# Main.net
KiCad netlist of a schematic drawn in Altium Designer
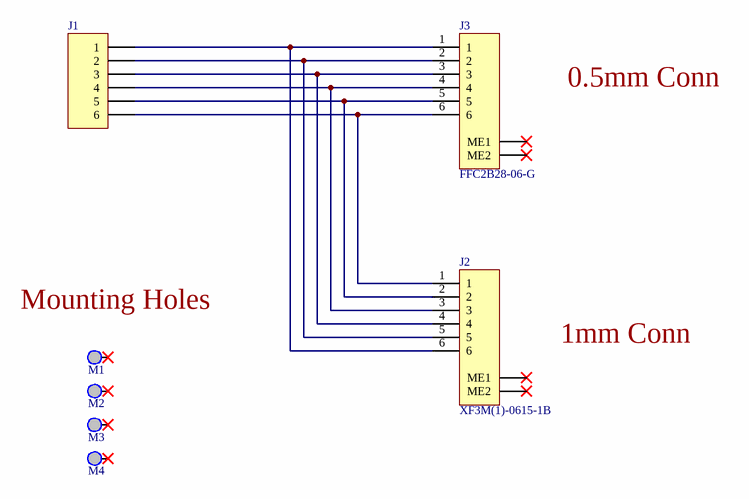
[diagram p0: Main.SchDoc]

(export (version "E")
  (design (tool "Eeschema 10.0.6"))
  (components
    (comp (ref "J1")
      (value "61300611121")
      (footprint "HDR-V-1X6")
      (description "Header, 6-Pin, 0.1\"")
      (libsource (lib "intercreate") (part "HDR-V-1X6-M"))
    )
    (comp (ref "J2")
      (value "XF3M(1)-0615-1B")
      (footprint "CONN-FFC-H-6P-1MM")
      (description "1.0-mm Pitch, Dual Contact ; For FPC/FFC, 6 Contacts, RoHS")
      (libsource (lib "intercreate") (part "CONN-FFC-H-6P-1MM"))
    )
    (comp (ref "J3")
      (value "FFC2B28-06-G")
      (footprint "CONN-FFC-H-6P-0.5MM")
      (description "6 Position FFC, FPC Connector Contacts, Top and Bottom 0.020\" (0.50mm) Surface Mount, Right Angle")
      (libsource (lib "intercreate") (part "CONN-FFC-H-6P-0.5MM"))
    )
    (comp (ref "M1")
      (value "MTG_HOLE")
      (footprint "MH_P_2.5MM")
      (description "MTG HOLE PLATED VARIOUS SIZES")
      (libsource (lib "intercreate") (part "MTG_HOLE"))
    )
    (comp (ref "M2")
      (value "MTG_HOLE")
      (footprint "MH_P_2.5MM")
      (description "MTG HOLE PLATED VARIOUS SIZES")
      (libsource (lib "intercreate") (part "MTG_HOLE"))
    )
    (comp (ref "M3")
      (value "MTG_HOLE")
      (footprint "MH_P_2.5MM")
      (description "MTG HOLE PLATED VARIOUS SIZES")
      (libsource (lib "intercreate") (part "MTG_HOLE"))
    )
    (comp (ref "M4")
      (value "MTG_HOLE")
      (footprint "MH_P_2.5MM")
      (description "MTG HOLE PLATED VARIOUS SIZES")
      (libsource (lib "intercreate") (part "MTG_HOLE"))
    )
  )
  (nets
    (net (code "1") (name "Net-(J1-Pad1)") (class "Default")
      (node (ref "J1") (pin "1") (pinfunction "1_1") (pintype "passive"))
      (node (ref "J2") (pin "6") (pinfunction "6_6") (pintype "passive"))
      (node (ref "J3") (pin "1") (pinfunction "1_1") (pintype "passive"))
    )
    (net (code "2") (name "Net-(J1-Pad2)") (class "Default")
      (node (ref "J1") (pin "2") (pinfunction "2_2") (pintype "passive"))
      (node (ref "J2") (pin "5") (pinfunction "5_5") (pintype "passive"))
      (node (ref "J3") (pin "2") (pinfunction "2_2") (pintype "passive"))
    )
    (net (code "3") (name "Net-(J1-Pad3)") (class "Default")
      (node (ref "J1") (pin "3") (pinfunction "3_3") (pintype "passive"))
      (node (ref "J2") (pin "4") (pinfunction "4_4") (pintype "passive"))
      (node (ref "J3") (pin "3") (pinfunction "3_3") (pintype "passive"))
    )
    (net (code "4") (name "Net-(J1-Pad4)") (class "Default")
      (node (ref "J1") (pin "4") (pinfunction "4_4") (pintype "passive"))
      (node (ref "J2") (pin "3") (pinfunction "3_3") (pintype "passive"))
      (node (ref "J3") (pin "4") (pinfunction "4_4") (pintype "passive"))
    )
    (net (code "5") (name "Net-(J1-Pad5)") (class "Default")
      (node (ref "J1") (pin "5") (pinfunction "5_5") (pintype "passive"))
      (node (ref "J2") (pin "2") (pinfunction "2_2") (pintype "passive"))
      (node (ref "J3") (pin "5") (pinfunction "5_5") (pintype "passive"))
    )
    (net (code "6") (name "Net-(J1-Pad6)") (class "Default")
      (node (ref "J1") (pin "6") (pinfunction "6_6") (pintype "passive"))
      (node (ref "J2") (pin "1") (pinfunction "1_1") (pintype "passive"))
      (node (ref "J3") (pin "6") (pinfunction "6_6") (pintype "passive"))
    )
    (net (code "7") (name "unconnected-(J2-PadME1)") (class "Default")
      (node (ref "J2") (pin "ME1") (pinfunction "ME1_ME1") (pintype "passive+no_connect"))
    )
    (net (code "8") (name "unconnected-(J2-PadME2)") (class "Default")
      (node (ref "J2") (pin "ME2") (pinfunction "ME2_ME2") (pintype "passive+no_connect"))
    )
    (net (code "9") (name "unconnected-(J3-PadME1)") (class "Default")
      (node (ref "J3") (pin "ME1") (pinfunction "ME1_ME1") (pintype "passive+no_connect"))
    )
    (net (code "10") (name "unconnected-(J3-PadME2)") (class "Default")
      (node (ref "J3") (pin "ME2") (pinfunction "ME2_ME2") (pintype "passive+no_connect"))
    )
    (net (code "11") (name "unconnected-(M1-Pad1)") (class "Default")
      (node (ref "M1") (pin "1") (pinfunction "1_1") (pintype "passive+no_connect"))
    )
    (net (code "12") (name "unconnected-(M2-Pad1)") (class "Default")
      (node (ref "M2") (pin "1") (pinfunction "1_1") (pintype "passive+no_connect"))
    )
    (net (code "13") (name "unconnected-(M3-Pad1)") (class "Default")
      (node (ref "M3") (pin "1") (pinfunction "1_1") (pintype "passive+no_connect"))
    )
    (net (code "14") (name "unconnected-(M4-Pad1)") (class "Default")
      (node (ref "M4") (pin "1") (pinfunction "1_1") (pintype "passive+no_connect"))
    )
  )
)
